# AMP.net
KiCad netlist of a schematic drawn in EAGLE
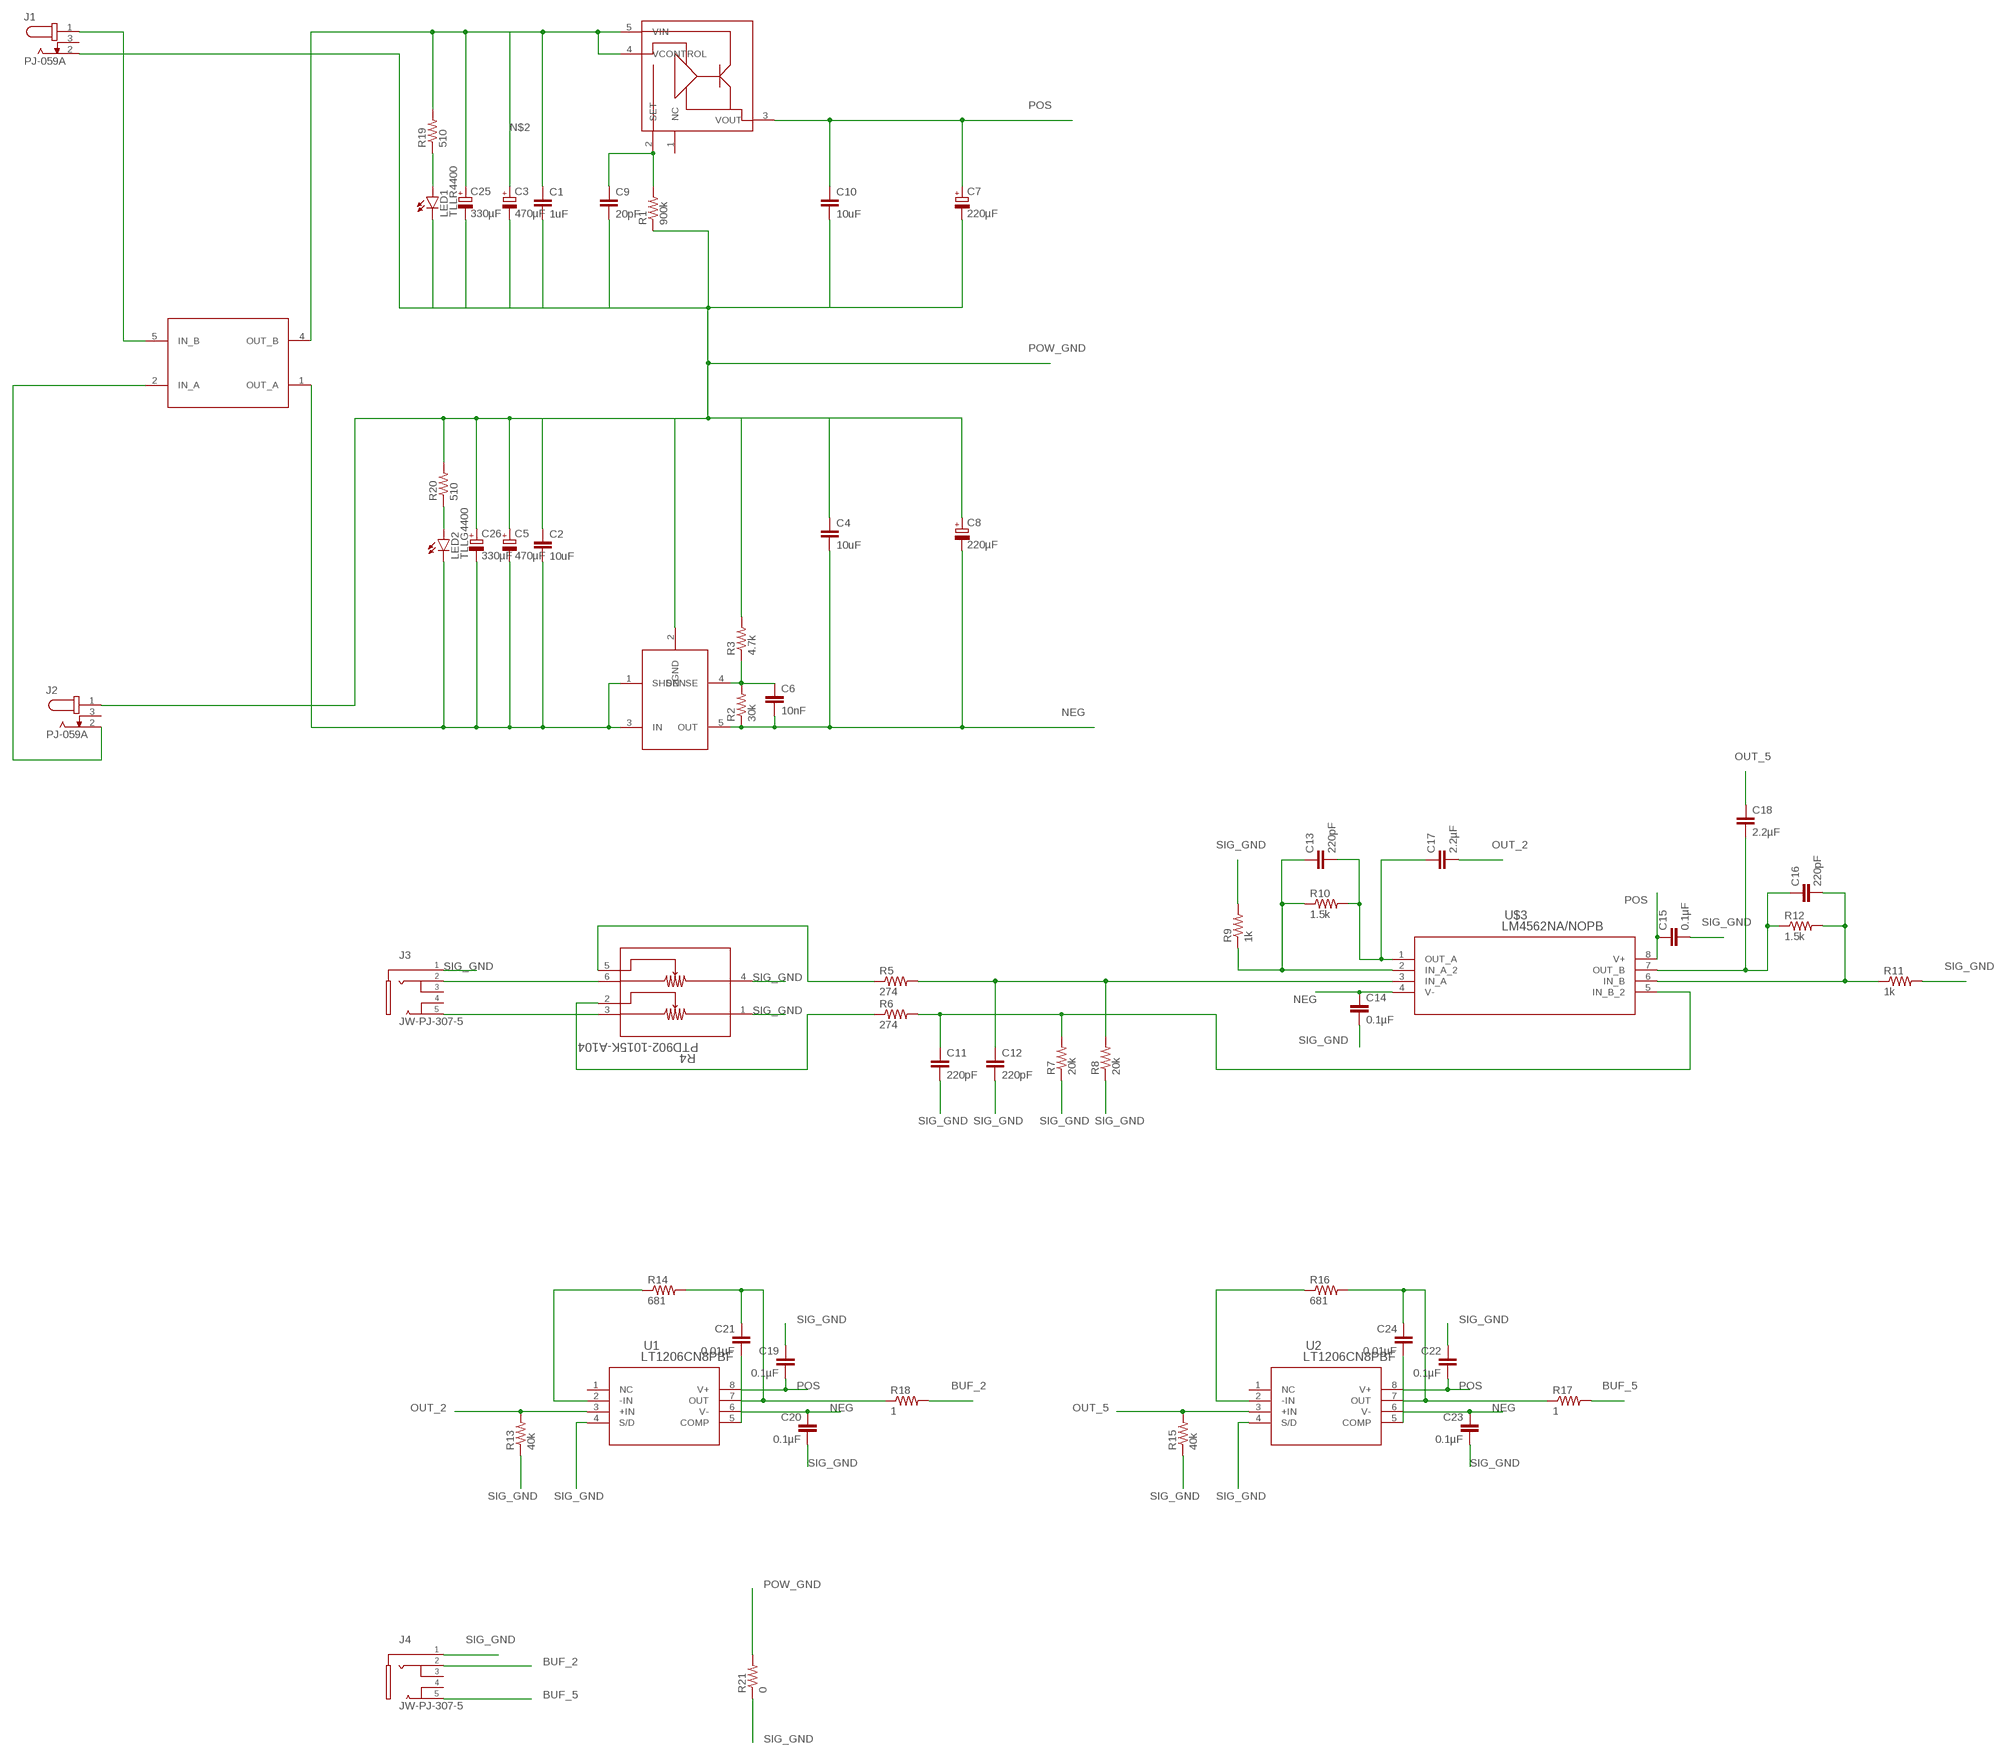
[diagram p0: schematic, sheet 1]

(export (version "E")
  (design (tool "Eeschema 10.0.6"))
  (components
    (comp (ref "C1")
      (value "1uF")
      (footprint "eagle-import:C050-025X075")
      (libsource (lib "eagle-import") (part "C-EU050-025X075"))
    )
    (comp (ref "C2")
      (value "10uF")
      (footprint "eagle-import:C050-025X075")
      (libsource (lib "eagle-import") (part "C-EU050-025X075"))
    )
    (comp (ref "C3")
      (value "470µF")
      (footprint "eagle-import:E3,5-8")
      (libsource (lib "eagle-import") (part "CPOL-EUE3.5-8"))
    )
    (comp (ref "C4")
      (value "10uF")
      (footprint "eagle-import:C050-025X075")
      (libsource (lib "eagle-import") (part "C-EU050-025X075"))
    )
    (comp (ref "C5")
      (value "470µF")
      (footprint "eagle-import:E3,5-8")
      (libsource (lib "eagle-import") (part "CPOL-EUE3.5-8"))
    )
    (comp (ref "C6")
      (value "10nF")
      (footprint "eagle-import:C025-025X050")
      (libsource (lib "eagle-import") (part "C-EU025-025X050"))
    )
    (comp (ref "C7")
      (value "220µF")
      (footprint "eagle-import:E3,5-8")
      (libsource (lib "eagle-import") (part "CPOL-EUE3.5-8"))
    )
    (comp (ref "C8")
      (value "220µF")
      (footprint "eagle-import:E3,5-8")
      (libsource (lib "eagle-import") (part "CPOL-EUE3.5-8"))
    )
    (comp (ref "C9")
      (value "20pF")
      (footprint "eagle-import:C025-025X050")
      (libsource (lib "eagle-import") (part "C-EU025-025X050"))
    )
    (comp (ref "C10")
      (value "10uF")
      (footprint "eagle-import:C050-025X075")
      (libsource (lib "eagle-import") (part "C-EU050-025X075"))
    )
    (comp (ref "C11")
      (value "220pF")
      (footprint "eagle-import:C050-025X075")
      (libsource (lib "eagle-import") (part "C-EU050-025X075"))
    )
    (comp (ref "C12")
      (value "220pF")
      (footprint "eagle-import:C050-025X075")
      (libsource (lib "eagle-import") (part "C-EU050-025X075"))
    )
    (comp (ref "C13")
      (value "220pF")
      (footprint "eagle-import:C050-025X075")
      (libsource (lib "eagle-import") (part "C-EU050-025X075"))
    )
    (comp (ref "C14")
      (value "0.1µF")
      (footprint "eagle-import:C050-025X075")
      (libsource (lib "eagle-import") (part "C-EU050-025X075"))
    )
    (comp (ref "C15")
      (value "0.1µF")
      (footprint "eagle-import:C050-025X075")
      (libsource (lib "eagle-import") (part "C-EU050-025X075"))
    )
    (comp (ref "C16")
      (value "220pF")
      (footprint "eagle-import:C050-025X075")
      (libsource (lib "eagle-import") (part "C-EU050-025X075"))
    )
    (comp (ref "C17")
      (value "2.2µF")
      (footprint "eagle-import:C050-025X075")
      (libsource (lib "eagle-import") (part "C-EU050-025X075"))
    )
    (comp (ref "C18")
      (value "2.2µF")
      (footprint "eagle-import:C050-025X075")
      (libsource (lib "eagle-import") (part "C-EU050-025X075"))
    )
    (comp (ref "C19")
      (value "0.1µF")
      (footprint "eagle-import:C050-025X075")
      (libsource (lib "eagle-import") (part "C-EU050-025X075"))
    )
    (comp (ref "C20")
      (value "0.1µF")
      (footprint "eagle-import:C050-025X075")
      (libsource (lib "eagle-import") (part "C-EU050-025X075"))
    )
    (comp (ref "C21")
      (value "0.01µF")
      (footprint "eagle-import:C050-025X075")
      (libsource (lib "eagle-import") (part "C-EU050-025X075"))
    )
    (comp (ref "C22")
      (value "0.1µF")
      (footprint "eagle-import:C050-025X075")
      (libsource (lib "eagle-import") (part "C-EU050-025X075"))
    )
    (comp (ref "C23")
      (value "0.1µF")
      (footprint "eagle-import:C050-025X075")
      (libsource (lib "eagle-import") (part "C-EU050-025X075"))
    )
    (comp (ref "C24")
      (value "0.01µF")
      (footprint "eagle-import:C050-025X075")
      (libsource (lib "eagle-import") (part "C-EU050-025X075"))
    )
    (comp (ref "C25")
      (value "330µF")
      (footprint "eagle-import:E3,5-8")
      (libsource (lib "eagle-import") (part "CPOL-EUE3.5-8"))
    )
    (comp (ref "C26")
      (value "330µF")
      (footprint "eagle-import:E3,5-8")
      (libsource (lib "eagle-import") (part "CPOL-EUE3.5-8"))
    )
    (comp (ref "J1")
      (value "PJ-059A")
      (footprint "eagle-import:CUI_PJ-059A")
      (fields (field (name "MF") "CUI Devices"))
      (libsource (lib "eagle-import") (part "PJ-059A"))
    )
    (comp (ref "J2")
      (value "PJ-059A")
      (footprint "eagle-import:CUI_PJ-059A")
      (fields (field (name "MF") "CUI Devices"))
      (libsource (lib "eagle-import") (part "PJ-059A"))
    )
    (comp (ref "J3")
      (value "JW-PJ-307-5")
      (footprint "eagle-import:JW-PJ-307-X")
      (libsource (lib "eagle-import") (part "JW-PJ-307-5"))
    )
    (comp (ref "J4")
      (value "JW-PJ-307-5")
      (footprint "eagle-import:JW-PJ-307-X")
      (libsource (lib "eagle-import") (part "JW-PJ-307-5"))
    )
    (comp (ref "LED1")
      (value "TLLR4400")
      (footprint "eagle-import:LED3MM")
      (fields (field (name "MF") "VISHAY SEMICONDUCTOR"))
      (libsource (lib "eagle-import") (part "TLLR4400"))
    )
    (comp (ref "LED2")
      (value "TLLG4400")
      (footprint "eagle-import:LED3MM")
      (fields (field (name "MF") "VISHAY SEMICONDUCTOR"))
      (libsource (lib "eagle-import") (part "TLLG4400"))
    )
    (comp (ref "R1")
      (value "900k")
      (footprint "eagle-import:0207_10")
      (libsource (lib "eagle-import") (part "R-US_0207/10"))
    )
    (comp (ref "R2")
      (value "30k")
      (footprint "eagle-import:0207_10")
      (libsource (lib "eagle-import") (part "R-US_0207/10"))
    )
    (comp (ref "R3")
      (value "4.7k")
      (footprint "eagle-import:0207_10")
      (libsource (lib "eagle-import") (part "R-US_0207/10"))
    )
    (comp (ref "R4")
      (value "PTD902-1015K-A104")
      (footprint "eagle-import:PTD902-15K_BRN")
      (fields (field (name "COPYRIGHT") "Copyright (C) 2018 Accelerated Designs. All rights reserved"))
      (libsource (lib "eagle-import") (part "PTD902-1015K-A104"))
    )
    (comp (ref "R5")
      (value "274")
      (footprint "eagle-import:0207_10")
      (libsource (lib "eagle-import") (part "R-US_0207/10"))
    )
    (comp (ref "R6")
      (value "274")
      (footprint "eagle-import:0207_10")
      (libsource (lib "eagle-import") (part "R-US_0207/10"))
    )
    (comp (ref "R7")
      (value "20k")
      (footprint "eagle-import:0207_10")
      (libsource (lib "eagle-import") (part "R-US_0207/10"))
    )
    (comp (ref "R8")
      (value "20k")
      (footprint "eagle-import:0207_10")
      (libsource (lib "eagle-import") (part "R-US_0207/10"))
    )
    (comp (ref "R9")
      (value "1k")
      (footprint "eagle-import:0207_10")
      (libsource (lib "eagle-import") (part "R-US_0207/10"))
    )
    (comp (ref "R10")
      (value "1.5k")
      (footprint "eagle-import:0207_10")
      (libsource (lib "eagle-import") (part "R-US_0207/10"))
    )
    (comp (ref "R11")
      (value "1k")
      (footprint "eagle-import:0207_10")
      (libsource (lib "eagle-import") (part "R-US_0207/10"))
    )
    (comp (ref "R12")
      (value "1.5k")
      (footprint "eagle-import:0207_10")
      (libsource (lib "eagle-import") (part "R-US_0207/10"))
    )
    (comp (ref "R13")
      (value "40k")
      (footprint "eagle-import:0207_10")
      (libsource (lib "eagle-import") (part "R-US_0207/10"))
    )
    (comp (ref "R14")
      (value "681")
      (footprint "eagle-import:0207_10")
      (libsource (lib "eagle-import") (part "R-US_0207/10"))
    )
    (comp (ref "R15")
      (value "40k")
      (footprint "eagle-import:0207_10")
      (libsource (lib "eagle-import") (part "R-US_0207/10"))
    )
    (comp (ref "R16")
      (value "681")
      (footprint "eagle-import:0207_10")
      (libsource (lib "eagle-import") (part "R-US_0207/10"))
    )
    (comp (ref "R17")
      (value "1")
      (footprint "eagle-import:0207_10")
      (libsource (lib "eagle-import") (part "R-US_0207/10"))
    )
    (comp (ref "R18")
      (value "1")
      (footprint "eagle-import:0207_10")
      (libsource (lib "eagle-import") (part "R-US_0207/10"))
    )
    (comp (ref "R19")
      (value "510")
      (footprint "eagle-import:0207_10")
      (libsource (lib "eagle-import") (part "R-US_0207/10"))
    )
    (comp (ref "R20")
      (value "510")
      (footprint "eagle-import:0207_10")
      (libsource (lib "eagle-import") (part "R-US_0207/10"))
    )
    (comp (ref "R21")
      (value "0")
      (footprint "eagle-import:0207_10")
      (libsource (lib "eagle-import") (part "R-US_0207/10"))
    )
    (comp (ref "SWITCH1")
      (value "M2022")
      (footprint "eagle-import:M2022")
      (libsource (lib "eagle-import") (part "M2022"))
    )
    (comp (ref "U$1")
      (value "LT3080")
      (footprint "eagle-import:TO220-5")
      (libsource (lib "eagle-import") (part "LT3080"))
    )
    (comp (ref "U$2")
      (value "LT3015LT3015")
      (footprint "eagle-import:TO220-5")
      (libsource (lib "eagle-import") (part "LT3015LT3015"))
    )
    (comp (ref "U$3")
      (value "LM4562NA/NOPB")
      (footprint "eagle-import:N08E")
      (libsource (lib "eagle-import") (part "LM4562NA/NOPB"))
    )
    (comp (ref "U1")
      (value "LT1206CN8PBF")
      (footprint "eagle-import:PDIP-8_N_LIT")
      (fields (field (name "MANUFACTURER_PART_NUMBER") "LT1206CN8#PBF"))
      (libsource (lib "eagle-import") (part "LT1206CN8PBF"))
    )
    (comp (ref "U2")
      (value "LT1206CN8PBF")
      (footprint "eagle-import:PDIP-8_N_LIT")
      (fields (field (name "MANUFACTURER_PART_NUMBER") "LT1206CN8#PBF"))
      (libsource (lib "eagle-import") (part "LT1206CN8PBF"))
    )
  )
  (nets
    (net (code "1") (name "/BUF_2") (class "Default")
      (node (ref "J4") (pin "P$2") (pinfunction "2_P$2") (pintype "passive"))
      (node (ref "R18") (pin "2") (pinfunction "2_2") (pintype "passive"))
    )
    (net (code "2") (name "/BUF_5") (class "Default")
      (node (ref "J4") (pin "P$4") (pinfunction "5_P$4") (pintype "passive"))
      (node (ref "R17") (pin "2") (pinfunction "2_2") (pintype "passive"))
    )
    (net (code "3") (name "/N$2") (class "Default")
      (node (ref "C1") (pin "1") (pinfunction "1_1") (pintype "passive"))
      (node (ref "C25") (pin "+") (pinfunction "+_+") (pintype "passive"))
      (node (ref "C3") (pin "+") (pinfunction "+_+") (pintype "passive"))
      (node (ref "R19") (pin "2") (pinfunction "2_2") (pintype "passive"))
      (node (ref "SWITCH1") (pin "4") (pinfunction "OUT_B_4") (pintype "bidirectional"))
      (node (ref "U$1") (pin "4") (pinfunction "VCONTROL_4") (pintype "input"))
      (node (ref "U$1") (pin "5") (pinfunction "VIN_5") (pintype "power_in"))
    )
    (net (code "4") (name "/NEG") (class "Default")
      (node (ref "C14") (pin "1") (pinfunction "1_1") (pintype "passive"))
      (node (ref "C20") (pin "1") (pinfunction "1_1") (pintype "passive"))
      (node (ref "C23") (pin "1") (pinfunction "1_1") (pintype "passive"))
      (node (ref "C4") (pin "2") (pinfunction "2_2") (pintype "passive"))
      (node (ref "C6") (pin "2") (pinfunction "2_2") (pintype "passive"))
      (node (ref "C8") (pin "-") (pinfunction "-_-") (pintype "passive"))
      (node (ref "R2") (pin "1") (pinfunction "1_1") (pintype "passive"))
      (node (ref "U$2") (pin "5") (pinfunction "OUT_5") (pintype "bidirectional"))
      (node (ref "U$3") (pin "4") (pinfunction "V-_4") (pintype "power_in"))
      (node (ref "U1") (pin "6") (pinfunction "V-_6") (pintype "power_in"))
      (node (ref "U2") (pin "6") (pinfunction "V-_6") (pintype "power_in"))
    )
    (net (code "5") (name "/OUT_2") (class "Default")
      (node (ref "C17") (pin "2") (pinfunction "2_2") (pintype "passive"))
      (node (ref "R13") (pin "2") (pinfunction "2_2") (pintype "passive"))
      (node (ref "U1") (pin "3") (pinfunction "+IN_3") (pintype "input"))
    )
    (net (code "6") (name "/OUT_5") (class "Default")
      (node (ref "C18") (pin "1") (pinfunction "1_1") (pintype "passive"))
      (node (ref "R15") (pin "2") (pinfunction "2_2") (pintype "passive"))
      (node (ref "U2") (pin "3") (pinfunction "+IN_3") (pintype "input"))
    )
    (net (code "7") (name "/POS") (class "Default")
      (node (ref "C10") (pin "1") (pinfunction "1_1") (pintype "passive"))
      (node (ref "C15") (pin "1") (pinfunction "1_1") (pintype "passive"))
      (node (ref "C19") (pin "2") (pinfunction "2_2") (pintype "passive"))
      (node (ref "C22") (pin "2") (pinfunction "2_2") (pintype "passive"))
      (node (ref "C7") (pin "+") (pinfunction "+_+") (pintype "passive"))
      (node (ref "U$1") (pin "3") (pinfunction "VOUT_3") (pintype "power_in"))
      (node (ref "U$3") (pin "8") (pinfunction "V+_8") (pintype "power_in"))
      (node (ref "U1") (pin "8") (pinfunction "V+_8") (pintype "power_in"))
      (node (ref "U2") (pin "8") (pinfunction "V+_8") (pintype "power_in"))
    )
    (net (code "8") (name "/POW_GND") (class "Default")
      (node (ref "C1") (pin "2") (pinfunction "2_2") (pintype "passive"))
      (node (ref "C10") (pin "2") (pinfunction "2_2") (pintype "passive"))
      (node (ref "C2") (pin "1") (pinfunction "1_1") (pintype "passive"))
      (node (ref "C25") (pin "-") (pinfunction "-_-") (pintype "passive"))
      (node (ref "C26") (pin "+") (pinfunction "+_+") (pintype "passive"))
      (node (ref "C3") (pin "-") (pinfunction "-_-") (pintype "passive"))
      (node (ref "C4") (pin "1") (pinfunction "1_1") (pintype "passive"))
      (node (ref "C5") (pin "+") (pinfunction "+_+") (pintype "passive"))
      (node (ref "C7") (pin "-") (pinfunction "-_-") (pintype "passive"))
      (node (ref "C8") (pin "+") (pinfunction "+_+") (pintype "passive"))
      (node (ref "C9") (pin "2") (pinfunction "2_2") (pintype "passive"))
      (node (ref "J1") (pin "2") (pinfunction "2_2") (pintype "passive"))
      (node (ref "J2") (pin "1") (pinfunction "1_1") (pintype "passive"))
      (node (ref "LED1") (pin "K") (pinfunction "C_K") (pintype "passive"))
      (node (ref "R1") (pin "1") (pinfunction "1_1") (pintype "passive"))
      (node (ref "R20") (pin "2") (pinfunction "2_2") (pintype "passive"))
      (node (ref "R21") (pin "2") (pinfunction "2_2") (pintype "passive"))
      (node (ref "R3") (pin "2") (pinfunction "2_2") (pintype "passive"))
      (node (ref "U$2") (pin "2") (pinfunction "GND_2") (pintype "bidirectional"))
    )
    (net (code "9") (name "/SIG_GND") (class "Default")
      (node (ref "C11") (pin "2") (pinfunction "2_2") (pintype "passive"))
      (node (ref "C12") (pin "2") (pinfunction "2_2") (pintype "passive"))
      (node (ref "C14") (pin "2") (pinfunction "2_2") (pintype "passive"))
      (node (ref "C15") (pin "2") (pinfunction "2_2") (pintype "passive"))
      (node (ref "C19") (pin "1") (pinfunction "1_1") (pintype "passive"))
      (node (ref "C20") (pin "2") (pinfunction "2_2") (pintype "passive"))
      (node (ref "C22") (pin "1") (pinfunction "1_1") (pintype "passive"))
      (node (ref "C23") (pin "2") (pinfunction "2_2") (pintype "passive"))
      (node (ref "J3") (pin "P$5") (pinfunction "1_P$5") (pintype "passive"))
      (node (ref "J4") (pin "P$5") (pinfunction "1_P$5") (pintype "passive"))
      (node (ref "R11") (pin "2") (pinfunction "2_2") (pintype "passive"))
      (node (ref "R13") (pin "1") (pinfunction "1_1") (pintype "passive"))
      (node (ref "R15") (pin "1") (pinfunction "1_1") (pintype "passive"))
      (node (ref "R21") (pin "1") (pinfunction "1_1") (pintype "passive"))
      (node (ref "R4") (pin "1") (pinfunction "1_1") (pintype "passive"))
      (node (ref "R4") (pin "4") (pinfunction "4_4") (pintype "passive"))
      (node (ref "R7") (pin "1") (pinfunction "1_1") (pintype "passive"))
      (node (ref "R8") (pin "1") (pinfunction "1_1") (pintype "passive"))
      (node (ref "R9") (pin "2") (pinfunction "2_2") (pintype "passive"))
      (node (ref "U1") (pin "4") (pinfunction "S/D_4") (pintype "passive"))
      (node (ref "U2") (pin "4") (pinfunction "S/D_4") (pintype "passive"))
    )
    (net (code "10") (name "Net-(J3-2)") (class "Default")
      (node (ref "J3") (pin "P$2") (pinfunction "2_P$2") (pintype "passive"))
      (node (ref "R4") (pin "6") (pinfunction "6_6") (pintype "passive"))
    )
    (net (code "11") (name "Net-(J3-5)") (class "Default")
      (node (ref "J3") (pin "P$4") (pinfunction "5_P$4") (pintype "passive"))
      (node (ref "R4") (pin "3") (pinfunction "3_3") (pintype "passive"))
    )
    (net (code "12") (name "Net-(LED1-PadA)") (class "Default")
      (node (ref "LED1") (pin "A") (pinfunction "A_A") (pintype "passive"))
      (node (ref "R19") (pin "1") (pinfunction "1_1") (pintype "passive"))
    )
    (net (code "13") (name "Net-(LED2-C)") (class "Default")
      (node (ref "C2") (pin "2") (pinfunction "2_2") (pintype "passive"))
      (node (ref "C26") (pin "-") (pinfunction "-_-") (pintype "passive"))
      (node (ref "C5") (pin "-") (pinfunction "-_-") (pintype "passive"))
      (node (ref "LED2") (pin "K") (pinfunction "C_K") (pintype "passive"))
      (node (ref "SWITCH1") (pin "1") (pinfunction "OUT_A_1") (pintype "bidirectional"))
      (node (ref "U$2") (pin "1") (pinfunction "SHDN_1") (pintype "bidirectional"))
      (node (ref "U$2") (pin "3") (pinfunction "IN_3") (pintype "bidirectional"))
    )
    (net (code "14") (name "Net-(LED2-PadA)") (class "Default")
      (node (ref "LED2") (pin "A") (pinfunction "A_A") (pintype "passive"))
      (node (ref "R20") (pin "1") (pinfunction "1_1") (pintype "passive"))
    )
    (net (code "15") (name "Net-(R4-Pad2)") (class "Default")
      (node (ref "R4") (pin "2") (pinfunction "2_2") (pintype "passive"))
      (node (ref "R6") (pin "1") (pinfunction "1_1") (pintype "passive"))
    )
    (net (code "16") (name "Net-(R4-Pad5)") (class "Default")
      (node (ref "R4") (pin "5") (pinfunction "5_5") (pintype "passive"))
      (node (ref "R5") (pin "1") (pinfunction "1_1") (pintype "passive"))
    )
    (net (code "17") (name "Net-(SWITCH1-IN_A)") (class "Default")
      (node (ref "J2") (pin "2") (pinfunction "2_2") (pintype "passive"))
      (node (ref "SWITCH1") (pin "2") (pinfunction "IN_A_2") (pintype "bidirectional"))
    )
    (net (code "18") (name "Net-(SWITCH1-IN_B)") (class "Default")
      (node (ref "J1") (pin "1") (pinfunction "1_1") (pintype "passive"))
      (node (ref "SWITCH1") (pin "5") (pinfunction "IN_B_5") (pintype "bidirectional"))
    )
    (net (code "19") (name "Net-(U$1-SET)") (class "Default")
      (node (ref "C9") (pin "1") (pinfunction "1_1") (pintype "passive"))
      (node (ref "R1") (pin "2") (pinfunction "2_2") (pintype "passive"))
      (node (ref "U$1") (pin "2") (pinfunction "SET_2") (pintype "input"))
    )
    (net (code "20") (name "Net-(U$2-SENSE)") (class "Default")
      (node (ref "C6") (pin "1") (pinfunction "1_1") (pintype "passive"))
      (node (ref "R2") (pin "2") (pinfunction "2_2") (pintype "passive"))
      (node (ref "R3") (pin "1") (pinfunction "1_1") (pintype "passive"))
      (node (ref "U$2") (pin "4") (pinfunction "SENSE_4") (pintype "bidirectional"))
    )
    (net (code "21") (name "Net-(U$3-IN_A)") (class "Default")
      (node (ref "C12") (pin "1") (pinfunction "1_1") (pintype "passive"))
      (node (ref "R5") (pin "2") (pinfunction "2_2") (pintype "passive"))
      (node (ref "R8") (pin "2") (pinfunction "2_2") (pintype "passive"))
      (node (ref "U$3") (pin "3") (pinfunction "IN_A_3") (pintype "input"))
    )
    (net (code "22") (name "Net-(U$3-IN_A_2)") (class "Default")
      (node (ref "C13") (pin "1") (pinfunction "1_1") (pintype "passive"))
      (node (ref "R10") (pin "1") (pinfunction "1_1") (pintype "passive"))
      (node (ref "R9") (pin "1") (pinfunction "1_1") (pintype "passive"))
      (node (ref "U$3") (pin "2") (pinfunction "IN_A_2_2") (pintype "input"))
    )
    (net (code "23") (name "Net-(U$3-IN_B)") (class "Default")
      (node (ref "C16") (pin "2") (pinfunction "2_2") (pintype "passive"))
      (node (ref "R11") (pin "1") (pinfunction "1_1") (pintype "passive"))
      (node (ref "R12") (pin "2") (pinfunction "2_2") (pintype "passive"))
      (node (ref "U$3") (pin "6") (pinfunction "IN_B_6") (pintype "input"))
    )
    (net (code "24") (name "Net-(U$3-IN_B_2)") (class "Default")
      (node (ref "C11") (pin "1") (pinfunction "1_1") (pintype "passive"))
      (node (ref "R6") (pin "2") (pinfunction "2_2") (pintype "passive"))
      (node (ref "R7") (pin "2") (pinfunction "2_2") (pintype "passive"))
      (node (ref "U$3") (pin "5") (pinfunction "IN_B_2_5") (pintype "input"))
    )
    (net (code "25") (name "Net-(U$3-OUT_A)") (class "Default")
      (node (ref "C13") (pin "2") (pinfunction "2_2") (pintype "passive"))
      (node (ref "C17") (pin "1") (pinfunction "1_1") (pintype "passive"))
      (node (ref "R10") (pin "2") (pinfunction "2_2") (pintype "passive"))
      (node (ref "U$3") (pin "1") (pinfunction "OUT_A_1") (pintype "output"))
    )
    (net (code "26") (name "Net-(U$3-OUT_B)") (class "Default")
      (node (ref "C16") (pin "1") (pinfunction "1_1") (pintype "passive"))
      (node (ref "C18") (pin "2") (pinfunction "2_2") (pintype "passive"))
      (node (ref "R12") (pin "1") (pinfunction "1_1") (pintype "passive"))
      (node (ref "U$3") (pin "7") (pinfunction "OUT_B_7") (pintype "output"))
    )
    (net (code "27") (name "Net-(U1--IN)") (class "Default")
      (node (ref "R14") (pin "1") (pinfunction "1_1") (pintype "passive"))
      (node (ref "U1") (pin "2") (pinfunction "-IN_2") (pintype "input"))
    )
    (net (code "28") (name "Net-(U1-COMP)") (class "Default")
      (node (ref "C21") (pin "2") (pinfunction "2_2") (pintype "passive"))
      (node (ref "U1") (pin "5") (pinfunction "COMP_5") (pintype "passive"))
    )
    (net (code "29") (name "Net-(U1-OUT)") (class "Default")
      (node (ref "C21") (pin "1") (pinfunction "1_1") (pintype "passive"))
      (node (ref "R14") (pin "2") (pinfunction "2_2") (pintype "passive"))
      (node (ref "R18") (pin "1") (pinfunction "1_1") (pintype "passive"))
      (node (ref "U1") (pin "7") (pinfunction "OUT_7") (pintype "output"))
    )
    (net (code "30") (name "Net-(U2--IN)") (class "Default")
      (node (ref "R16") (pin "1") (pinfunction "1_1") (pintype "passive"))
      (node (ref "U2") (pin "2") (pinfunction "-IN_2") (pintype "input"))
    )
    (net (code "31") (name "Net-(U2-COMP)") (class "Default")
      (node (ref "C24") (pin "2") (pinfunction "2_2") (pintype "passive"))
      (node (ref "U2") (pin "5") (pinfunction "COMP_5") (pintype "passive"))
    )
    (net (code "32") (name "Net-(U2-OUT)") (class "Default")
      (node (ref "C24") (pin "1") (pinfunction "1_1") (pintype "passive"))
      (node (ref "R16") (pin "2") (pinfunction "2_2") (pintype "passive"))
      (node (ref "R17") (pin "1") (pinfunction "1_1") (pintype "passive"))
      (node (ref "U2") (pin "7") (pinfunction "OUT_7") (pintype "output"))
    )
    (net (code "33") (name "unconnected-(J1-Pad3)") (class "Default")
      (node (ref "J1") (pin "3") (pinfunction "3_3") (pintype "passive"))
    )
    (net (code "34") (name "unconnected-(J2-Pad3)") (class "Default")
      (node (ref "J2") (pin "3") (pinfunction "3_3") (pintype "passive"))
    )
    (net (code "35") (name "unconnected-(J3-3-PadP$1)") (class "Default")
      (node (ref "J3") (pin "P$1") (pinfunction "3_P$1") (pintype "passive"))
    )
    (net (code "36") (name "unconnected-(J3-4-PadP$3)") (class "Default")
      (node (ref "J3") (pin "P$3") (pinfunction "4_P$3") (pintype "passive"))
    )
    (net (code "37") (name "unconnected-(J4-3-PadP$1)") (class "Default")
      (node (ref "J4") (pin "P$1") (pinfunction "3_P$1") (pintype "passive"))
    )
    (net (code "38") (name "unconnected-(J4-4-PadP$3)") (class "Default")
      (node (ref "J4") (pin "P$3") (pinfunction "4_P$3") (pintype "passive"))
    )
    (net (code "39") (name "unconnected-(U$1-NC-Pad1)") (class "Default")
      (node (ref "U$1") (pin "1") (pinfunction "NC_1") (pintype "no_connect"))
    )
    (net (code "40") (name "unconnected-(U1-NC-Pad1)") (class "Default")
      (node (ref "U1") (pin "1") (pinfunction "NC_1") (pintype "passive"))
    )
    (net (code "41") (name "unconnected-(U2-NC-Pad1)") (class "Default")
      (node (ref "U2") (pin "1") (pinfunction "NC_1") (pintype "passive"))
    )
  )
)
